# 5VAC-DCReg.net
KiCad netlist of a schematic drawn in EAGLE
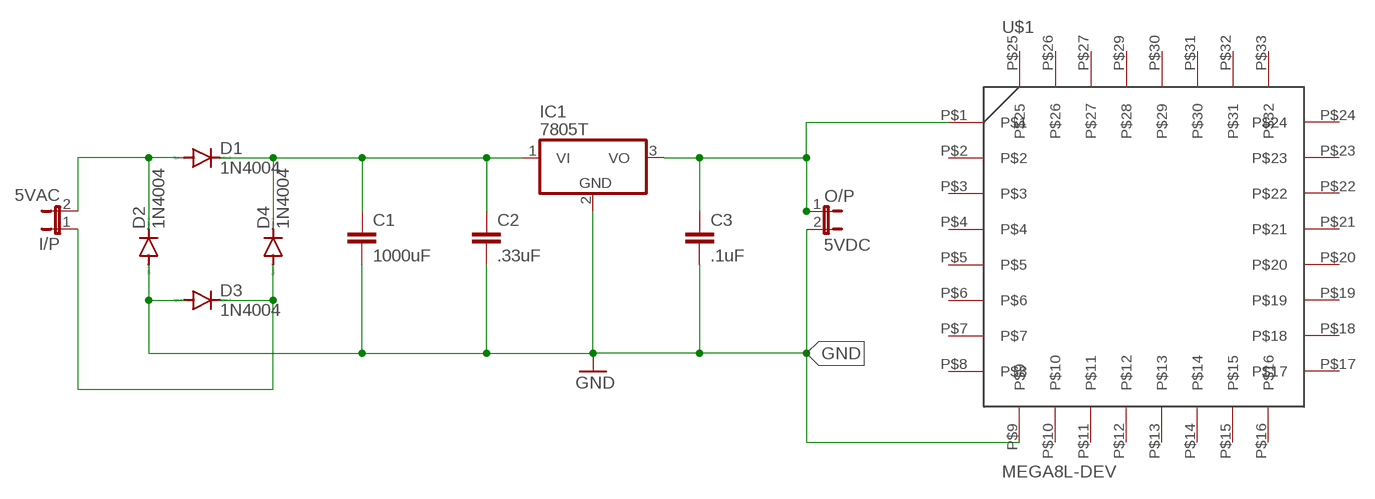
[diagram p0: schematic, sheet 1]

(export (version "E")
  (design (tool "Eeschema 10.0.6"))
  (components
    (comp (ref "C1")
      (value "1000uF")
      (footprint "eagle-import:C2.5-3")
      (libsource (lib "eagle-import") (part "C2,5-3"))
    )
    (comp (ref "C2")
      (value ".33uF")
      (footprint "eagle-import:C2.5-3")
      (libsource (lib "eagle-import") (part "C2,5-3"))
    )
    (comp (ref "C3")
      (value ".1uF")
      (footprint "eagle-import:C2.5-3")
      (libsource (lib "eagle-import") (part "C2,5-3"))
    )
    (comp (ref "D1")
      (value "1N4004")
      (footprint "eagle-import:DO41-10")
      (libsource (lib "eagle-import") (part "1N4004"))
    )
    (comp (ref "D2")
      (value "1N4004")
      (footprint "eagle-import:DO41-10")
      (libsource (lib "eagle-import") (part "1N4004"))
    )
    (comp (ref "D3")
      (value "1N4004")
      (footprint "eagle-import:DO41-10")
      (libsource (lib "eagle-import") (part "1N4004"))
    )
    (comp (ref "D4")
      (value "1N4004")
      (footprint "eagle-import:DO41-10")
      (libsource (lib "eagle-import") (part "1N4004"))
    )
    (comp (ref "I/P")
      (value "5VAC")
      (footprint "eagle-import:JP1")
      (libsource (lib "eagle-import") (part "JP1E"))
    )
    (comp (ref "IC1")
      (value "7805T")
      (footprint "eagle-import:TO220H")
      (libsource (lib "eagle-import") (part "78T05"))
    )
    (comp (ref "O/P")
      (value "5VDC")
      (footprint "eagle-import:JP1")
      (libsource (lib "eagle-import") (part "JP1E"))
    )
    (comp (ref "U$1")
      (value "MEGA8L-DEV")
      (footprint "eagle-import:TQFP-MEGA8L")
      (libsource (lib "eagle-import") (part "MEGA8L-DEV"))
    )
  )
  (nets
    (net (code "1") (name "GND") (class "Default")
      (node (ref "C1") (pin "2") (pinfunction "2_2") (pintype "passive"))
      (node (ref "C2") (pin "2") (pinfunction "2_2") (pintype "passive"))
      (node (ref "C3") (pin "2") (pinfunction "2_2") (pintype "passive"))
      (node (ref "D2") (pin "A") (pinfunction "A_A") (pintype "passive"))
      (node (ref "D3") (pin "A") (pinfunction "A_A") (pintype "passive"))
      (node (ref "IC1") (pin "2") (pinfunction "GND_2") (pintype "passive"))
      (node (ref "O/P") (pin "2") (pinfunction "2_2") (pintype "passive"))
      (node (ref "U$1") (pin "P$9") (pinfunction "P$9_P$9") (pintype "bidirectional"))
    )
    (net (code "2") (name "Net-(D1-PadA)") (class "Default")
      (node (ref "D1") (pin "A") (pinfunction "A_A") (pintype "passive"))
      (node (ref "D2") (pin "C") (pinfunction "C_C") (pintype "passive"))
      (node (ref "I/P") (pin "2") (pinfunction "2_2") (pintype "passive"))
    )
    (net (code "3") (name "Net-(D3-PadC)") (class "Default")
      (node (ref "D3") (pin "C") (pinfunction "C_C") (pintype "passive"))
      (node (ref "D4") (pin "A") (pinfunction "A_A") (pintype "passive"))
      (node (ref "I/P") (pin "1") (pinfunction "1_1") (pintype "passive"))
    )
    (net (code "4") (name "Net-(IC1-VI)") (class "Default")
      (node (ref "C1") (pin "1") (pinfunction "1_1") (pintype "passive"))
      (node (ref "C2") (pin "1") (pinfunction "1_1") (pintype "passive"))
      (node (ref "D1") (pin "C") (pinfunction "C_C") (pintype "passive"))
      (node (ref "D4") (pin "C") (pinfunction "C_C") (pintype "passive"))
      (node (ref "IC1") (pin "1") (pinfunction "VI_1") (pintype "input"))
    )
    (net (code "5") (name "Net-(IC1-VO)") (class "Default")
      (node (ref "C3") (pin "1") (pinfunction "1_1") (pintype "passive"))
      (node (ref "IC1") (pin "3") (pinfunction "VO_3") (pintype "passive"))
      (node (ref "O/P") (pin "1") (pinfunction "1_1") (pintype "passive"))
      (node (ref "U$1") (pin "P$1") (pinfunction "P$1_P$1") (pintype "bidirectional"))
    )
    (net (code "6") (name "unconnected-(U$1-P$28-PadP$29)") (class "Default")
      (node (ref "U$1") (pin "P$29") (pinfunction "P$28_P$29") (pintype "bidirectional"))
    )
    (net (code "7") (name "unconnected-(U$1-P$29-PadP$30)") (class "Default")
      (node (ref "U$1") (pin "P$30") (pinfunction "P$29_P$30") (pintype "bidirectional"))
    )
    (net (code "8") (name "unconnected-(U$1-P$30-PadP$31)") (class "Default")
      (node (ref "U$1") (pin "P$31") (pinfunction "P$30_P$31") (pintype "bidirectional"))
    )
    (net (code "9") (name "unconnected-(U$1-P$31-PadP$32)") (class "Default")
      (node (ref "U$1") (pin "P$32") (pinfunction "P$31_P$32") (pintype "bidirectional"))
    )
    (net (code "10") (name "unconnected-(U$1-P$32-PadP$33)") (class "Default")
      (node (ref "U$1") (pin "P$33") (pinfunction "P$32_P$33") (pintype "bidirectional"))
    )
    (net (code "11") (name "unconnected-(U$1-PadP$2)") (class "Default")
      (node (ref "U$1") (pin "P$2") (pinfunction "P$2_P$2") (pintype "bidirectional"))
    )
    (net (code "12") (name "unconnected-(U$1-PadP$3)") (class "Default")
      (node (ref "U$1") (pin "P$3") (pinfunction "P$3_P$3") (pintype "bidirectional"))
    )
    (net (code "13") (name "unconnected-(U$1-PadP$4)") (class "Default")
      (node (ref "U$1") (pin "P$4") (pinfunction "P$4_P$4") (pintype "bidirectional"))
    )
    (net (code "14") (name "unconnected-(U$1-PadP$5)") (class "Default")
      (node (ref "U$1") (pin "P$5") (pinfunction "P$5_P$5") (pintype "bidirectional"))
    )
    (net (code "15") (name "unconnected-(U$1-PadP$6)") (class "Default")
      (node (ref "U$1") (pin "P$6") (pinfunction "P$6_P$6") (pintype "bidirectional"))
    )
    (net (code "16") (name "unconnected-(U$1-PadP$7)") (class "Default")
      (node (ref "U$1") (pin "P$7") (pinfunction "P$7_P$7") (pintype "bidirectional"))
    )
    (net (code "17") (name "unconnected-(U$1-PadP$8)") (class "Default")
      (node (ref "U$1") (pin "P$8") (pinfunction "P$8_P$8") (pintype "bidirectional"))
    )
    (net (code "18") (name "unconnected-(U$1-PadP$10)") (class "Default")
      (node (ref "U$1") (pin "P$10") (pinfunction "P$10_P$10") (pintype "bidirectional"))
    )
    (net (code "19") (name "unconnected-(U$1-PadP$11)") (class "Default")
      (node (ref "U$1") (pin "P$11") (pinfunction "P$11_P$11") (pintype "bidirectional"))
    )
    (net (code "20") (name "unconnected-(U$1-PadP$12)") (class "Default")
      (node (ref "U$1") (pin "P$12") (pinfunction "P$12_P$12") (pintype "bidirectional"))
    )
    (net (code "21") (name "unconnected-(U$1-PadP$13)") (class "Default")
      (node (ref "U$1") (pin "P$13") (pinfunction "P$13_P$13") (pintype "bidirectional"))
    )
    (net (code "22") (name "unconnected-(U$1-PadP$14)") (class "Default")
      (node (ref "U$1") (pin "P$14") (pinfunction "P$14_P$14") (pintype "bidirectional"))
    )
    (net (code "23") (name "unconnected-(U$1-PadP$15)") (class "Default")
      (node (ref "U$1") (pin "P$15") (pinfunction "P$15_P$15") (pintype "bidirectional"))
    )
    (net (code "24") (name "unconnected-(U$1-PadP$16)") (class "Default")
      (node (ref "U$1") (pin "P$16") (pinfunction "P$16_P$16") (pintype "bidirectional"))
    )
    (net (code "25") (name "unconnected-(U$1-PadP$17)") (class "Default")
      (node (ref "U$1") (pin "P$17") (pinfunction "P$17_P$17") (pintype "bidirectional"))
    )
    (net (code "26") (name "unconnected-(U$1-PadP$18)") (class "Default")
      (node (ref "U$1") (pin "P$18") (pinfunction "P$18_P$18") (pintype "bidirectional"))
    )
    (net (code "27") (name "unconnected-(U$1-PadP$19)") (class "Default")
      (node (ref "U$1") (pin "P$19") (pinfunction "P$19_P$19") (pintype "bidirectional"))
    )
    (net (code "28") (name "unconnected-(U$1-PadP$20)") (class "Default")
      (node (ref "U$1") (pin "P$20") (pinfunction "P$20_P$20") (pintype "bidirectional"))
    )
    (net (code "29") (name "unconnected-(U$1-PadP$21)") (class "Default")
      (node (ref "U$1") (pin "P$21") (pinfunction "P$21_P$21") (pintype "bidirectional"))
    )
    (net (code "30") (name "unconnected-(U$1-PadP$22)") (class "Default")
      (node (ref "U$1") (pin "P$22") (pinfunction "P$22_P$22") (pintype "bidirectional"))
    )
    (net (code "31") (name "unconnected-(U$1-PadP$23)") (class "Default")
      (node (ref "U$1") (pin "P$23") (pinfunction "P$23_P$23") (pintype "bidirectional"))
    )
    (net (code "32") (name "unconnected-(U$1-PadP$24)") (class "Default")
      (node (ref "U$1") (pin "P$24") (pinfunction "P$24_P$24") (pintype "bidirectional"))
    )
    (net (code "33") (name "unconnected-(U$1-PadP$25)") (class "Default")
      (node (ref "U$1") (pin "P$25") (pinfunction "P$25_P$25") (pintype "bidirectional"))
    )
    (net (code "34") (name "unconnected-(U$1-PadP$26)") (class "Default")
      (node (ref "U$1") (pin "P$26") (pinfunction "P$26_P$26") (pintype "bidirectional"))
    )
    (net (code "35") (name "unconnected-(U$1-PadP$27)") (class "Default")
      (node (ref "U$1") (pin "P$27") (pinfunction "P$27_P$27") (pintype "bidirectional"))
    )
  )
)
